# dc_motor.net
KiCad netlist of a schematic drawn in Altium Designer
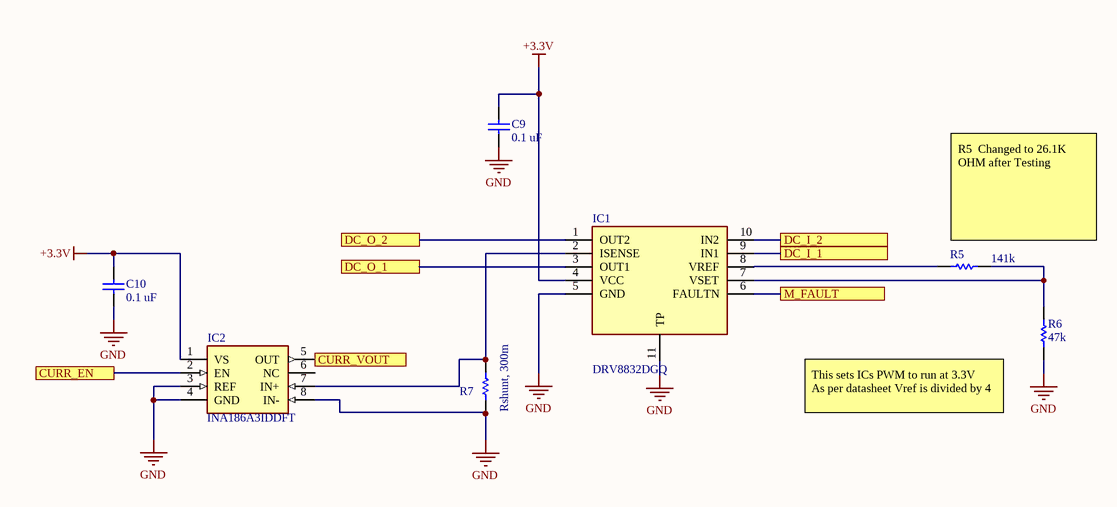
[diagram p0: dc_motor.SchDoc]

(export (version "E")
  (design (tool "Eeschema 10.0.6"))
  (components
    (comp (ref "C9")
      (value "0.1 uF")
      (footprint "CAPC2013X145X50LL20T25")
      (fields (field (name "MANUFACTURER") "Kemet") (field (name "PART NUMBER") "C0805C104Z5VACTU"))
      (libsource (lib "Altium Content Vault") (part "CAP"))
    )
    (comp (ref "C10")
      (value "0.1 uF")
      (footprint "CAPC2013X145X50LL20T25")
      (fields (field (name "MANUFACTURER") "Kemet") (field (name "PART NUMBER") "C0805C104Z5VACTU"))
      (libsource (lib "Altium Content Vault") (part "CAP"))
    )
    (comp (ref "IC1")
      (value "DRV8832DGQ")
      (footprint "SamacSys:SOP50P490X110-11N")
      (description "Integrated Circuit")
      (fields (field (name "MOUSER PART NUMBER") "595-DRV8832DGQ"))
      (libsource (lib "*") (part "DRV8832DGQ"))
    )
    (comp (ref "IC2")
      (value "INA186A3IDDFT")
      (footprint "SOT65P280X110-8N")
      (description "Integrated Circuit")
      (libsource (lib "*") (part "INA186A3IDDFT"))
    )
    (comp (ref "R5")
      (value "141k")
      (footprint "RESC2013X60X35NL10T20")
      (description "ERJ-6ENF1403V 141K")
      (fields (field (name "MANUFACTURER") "Yageo"))
      (libsource (lib "Altium Content Vault") (part "RES-2"))
    )
    (comp (ref "R6")
      (value "47k")
      (footprint "RESC2013X60X35NL10T20")
      (fields (field (name "MANUFACTURER") "Yageo"))
      (libsource (lib "Altium Content Vault") (part "RES-2"))
    )
    (comp (ref "R7")
      (value "Rshunt, 300m")
      (footprint "RESC3116X65X40ML10T20")
      (description "CSR1206FKR300\r\nRES 0.3 OHM 1% 1/2W 1206")
      (fields (field (name "TOLERANCE") "1%") (field (name "MANUFACTURER") "Yageo"))
      (libsource (lib "Altium Content Vault") (part "RES-2"))
    )
  )
  (nets
    (net (code "1") (name "+3.3V") (class "Default")
      (node (ref "C10") (pin "2") (pinfunction "2_2") (pintype "passive"))
      (node (ref "C9") (pin "2") (pinfunction "2_2") (pintype "passive"))
      (node (ref "IC1") (pin "4") (pinfunction "VCC_4") (pintype "passive"))
      (node (ref "IC2") (pin "1") (pinfunction "VS_1") (pintype "power_in"))
    )
    (net (code "2") (name "/CURR_EN") (class "Default")
      (node (ref "IC2") (pin "2") (pinfunction "EN_2") (pintype "input"))
    )
    (net (code "3") (name "/CURR_VOUT") (class "Default")
      (node (ref "IC2") (pin "5") (pinfunction "OUT_5") (pintype "output"))
    )
    (net (code "4") (name "/DC_I_1") (class "Default")
      (node (ref "IC1") (pin "9") (pinfunction "IN1_9") (pintype "passive"))
    )
    (net (code "5") (name "/DC_I_2") (class "Default")
      (node (ref "IC1") (pin "10") (pinfunction "IN2_10") (pintype "passive"))
    )
    (net (code "6") (name "/DC_O_1") (class "Default")
      (node (ref "IC1") (pin "3") (pinfunction "OUT1_3") (pintype "passive"))
    )
    (net (code "7") (name "/DC_O_2") (class "Default")
      (node (ref "IC1") (pin "1") (pinfunction "OUT2_1") (pintype "passive"))
    )
    (net (code "8") (name "/M_FAULT") (class "Default")
      (node (ref "IC1") (pin "6") (pinfunction "FAULTN_6") (pintype "passive"))
    )
    (net (code "9") (name "GND") (class "Default")
      (node (ref "C10") (pin "1") (pinfunction "1_1") (pintype "passive"))
      (node (ref "C9") (pin "1") (pinfunction "1_1") (pintype "passive"))
      (node (ref "IC1") (pin "11") (pinfunction "TP_11") (pintype "passive"))
      (node (ref "IC1") (pin "5") (pinfunction "GND_5") (pintype "passive"))
      (node (ref "IC2") (pin "3") (pinfunction "REF_3") (pintype "input"))
      (node (ref "IC2") (pin "4") (pinfunction "GND_4") (pintype "power_in"))
      (node (ref "IC2") (pin "8") (pinfunction "IN-_8") (pintype "input"))
      (node (ref "R6") (pin "1") (pinfunction "1_1") (pintype "passive"))
      (node (ref "R7") (pin "1") (pinfunction "1_1") (pintype "passive"))
    )
    (net (code "10") (name "Net-(IC1-ISENSE)") (class "Default")
      (node (ref "IC1") (pin "2") (pinfunction "ISENSE_2") (pintype "passive"))
      (node (ref "IC2") (pin "7") (pinfunction "IN+_7") (pintype "input"))
      (node (ref "R7") (pin "2") (pinfunction "2_2") (pintype "passive"))
    )
    (net (code "11") (name "Net-(IC1-VREF)") (class "Default")
      (node (ref "IC1") (pin "8") (pinfunction "VREF_8") (pintype "passive"))
      (node (ref "R5") (pin "2") (pinfunction "2_2") (pintype "passive"))
    )
    (net (code "12") (name "Net-(IC1-VSET)") (class "Default")
      (node (ref "IC1") (pin "7") (pinfunction "VSET_7") (pintype "passive"))
      (node (ref "R5") (pin "1") (pinfunction "1_1") (pintype "passive"))
      (node (ref "R6") (pin "2") (pinfunction "2_2") (pintype "passive"))
    )
    (net (code "13") (name "unconnected-(IC2-NC-Pad6)") (class "Default")
      (node (ref "IC2") (pin "6") (pinfunction "NC_6") (pintype "passive"))
    )
  )
)
